# Python.net
KiCad netlist of a schematic drawn in Altium Designer
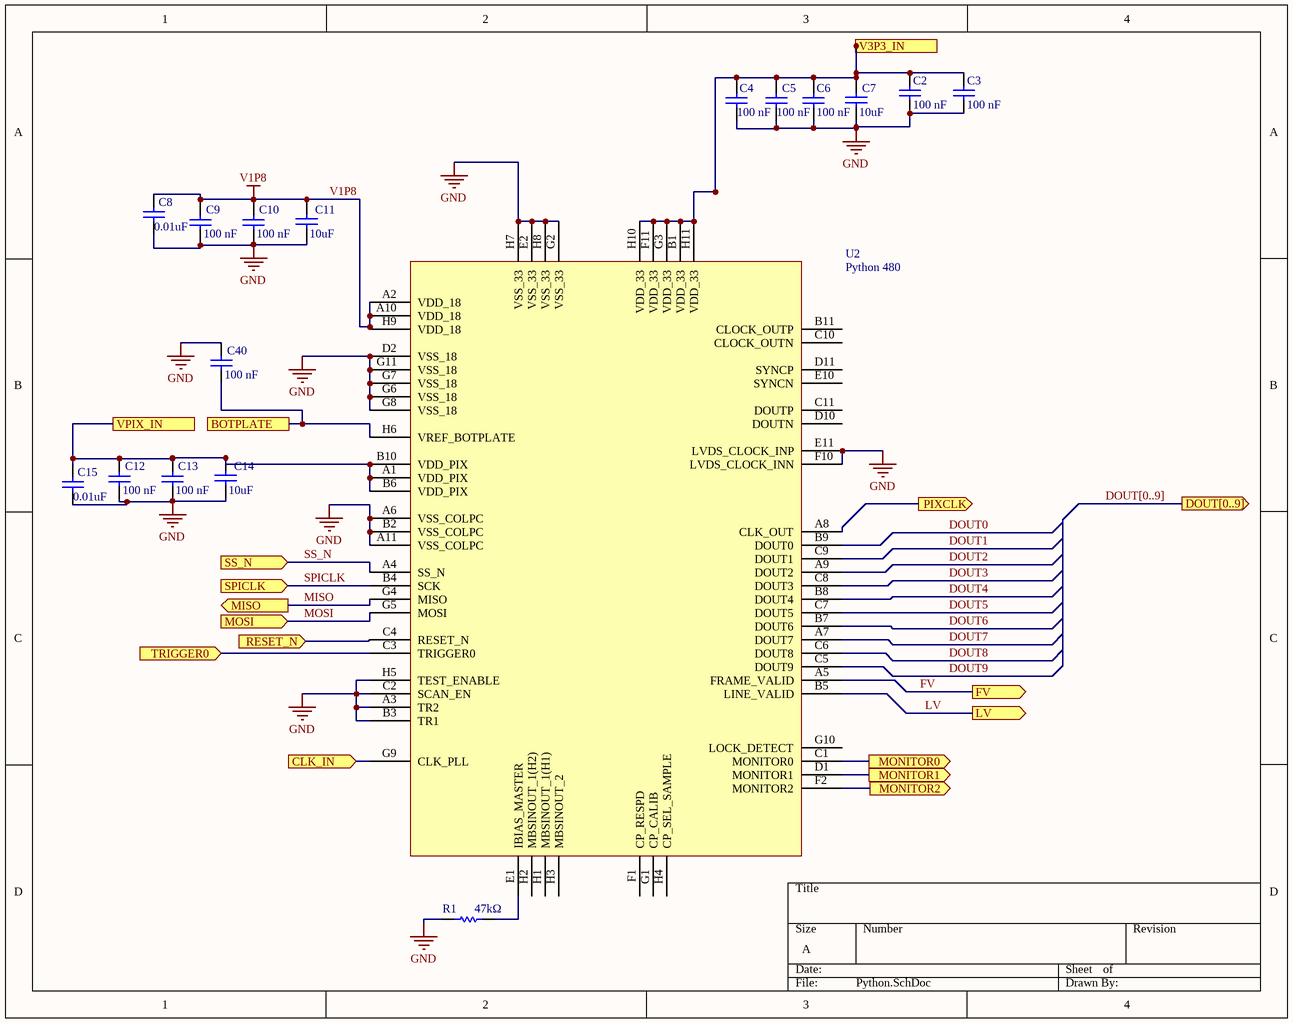
[diagram p0: Python.SchDoc]

(export (version "E")
  (design (tool "Eeschema 10.0.6"))
  (components
    (comp (ref "C2")
      (value "GRM033C71C104KE14D")
      (footprint "PCB-v6eq6etc9p7u7qdkgnno-1")
      (description "0.1 µF ±10% 16V Ceramic Capacitor X7S 0201 (0603 Metric)")
      (fields (field (name "CAPACITANCE") "100 nF"))
      (libsource (lib "Python_Imaging_1") (part "CMP-cc290632c88a13ee-3"))
    )
    (comp (ref "C3")
      (value "GRM033C71C104KE14D")
      (footprint "PCB-v6eq6etc9p7u7qdkgnno-1")
      (description "0.1 µF ±10% 16V Ceramic Capacitor X7S 0201 (0603 Metric)")
      (fields (field (name "CAPACITANCE") "100 nF"))
      (libsource (lib "Python_Imaging_1") (part "CMP-cc290632c88a13ee-3"))
    )
    (comp (ref "C4")
      (value "GRM033C71C104KE14D")
      (footprint "PCB-v6eq6etc9p7u7qdkgnno-1")
      (description "0.1 µF ±10% 16V Ceramic Capacitor X7S 0201 (0603 Metric)")
      (fields (field (name "CAPACITANCE") "100 nF"))
      (libsource (lib "Python_Imaging_1") (part "CMP-cc290632c88a13ee-3"))
    )
    (comp (ref "C5")
      (value "GRM033C71C104KE14D")
      (footprint "PCB-v6eq6etc9p7u7qdkgnno-1")
      (description "0.1 µF ±10% 16V Ceramic Capacitor X7S 0201 (0603 Metric)")
      (fields (field (name "CAPACITANCE") "100 nF"))
      (libsource (lib "Python_Imaging_1") (part "CMP-cc290632c88a13ee-3"))
    )
    (comp (ref "C6")
      (value "GRM033C71C104KE14D")
      (footprint "PCB-v6eq6etc9p7u7qdkgnno-1")
      (description "0.1 µF ±10% 16V Ceramic Capacitor X7S 0201 (0603 Metric)")
      (fields (field (name "CAPACITANCE") "100 nF"))
      (libsource (lib "Python_Imaging_1") (part "CMP-cc290632c88a13ee-3"))
    )
    (comp (ref "C7")
      (value "GRM155R61A106ME11D")
      (footprint "PCB-uspfzztrpe7hn2xlyjz9-1")
      (description "10 µF ±20% 10V Ceramic Capacitor X5R 0402 (1005 Metric)")
      (fields (field (name "CAPACITANCE") "10uF"))
      (libsource (lib "Python_Imaging_1") (part "CMP-eacb22ede71a350c-8"))
    )
    (comp (ref "C8")
      (value "GRM033R71A103KA01D")
      (footprint "PCB-v6eq6etc9p7u7qdkgnno-1")
      (description "10000 pF ±10% 10V Ceramic Capacitor X7R 0201 (0603 Metric)")
      (fields (field (name "CAPACITANCE") "0.01uF"))
      (libsource (lib "Python_Imaging_1") (part "CMP-19299660-4"))
    )
    (comp (ref "C9")
      (value "GRM033C71C104KE14D")
      (footprint "PCB-v6eq6etc9p7u7qdkgnno-1")
      (description "0.1 µF ±10% 16V Ceramic Capacitor X7S 0201 (0603 Metric)")
      (fields (field (name "CAPACITANCE") "100 nF"))
      (libsource (lib "Python_Imaging_1") (part "CMP-cc290632c88a13ee-3"))
    )
    (comp (ref "C10")
      (value "GRM033C71C104KE14D")
      (footprint "PCB-v6eq6etc9p7u7qdkgnno-1")
      (description "0.1 µF ±10% 16V Ceramic Capacitor X7S 0201 (0603 Metric)")
      (fields (field (name "CAPACITANCE") "100 nF"))
      (libsource (lib "Python_Imaging_1") (part "CMP-cc290632c88a13ee-3"))
    )
    (comp (ref "C11")
      (value "GRM155R61A106ME11D")
      (footprint "PCB-uspfzztrpe7hn2xlyjz9-1")
      (description "10 µF ±20% 10V Ceramic Capacitor X5R 0402 (1005 Metric)")
      (fields (field (name "CAPACITANCE") "10uF"))
      (libsource (lib "Python_Imaging_1") (part "CMP-eacb22ede71a350c-8"))
    )
    (comp (ref "C12")
      (value "GRM033C71C104KE14D")
      (footprint "PCB-v6eq6etc9p7u7qdkgnno-1")
      (description "0.1 µF ±10% 16V Ceramic Capacitor X7S 0201 (0603 Metric)")
      (fields (field (name "CAPACITANCE") "100 nF"))
      (libsource (lib "Python_Imaging_1") (part "CMP-cc290632c88a13ee-3"))
    )
    (comp (ref "C13")
      (value "GRM033C71C104KE14D")
      (footprint "PCB-v6eq6etc9p7u7qdkgnno-1")
      (description "0.1 µF ±10% 16V Ceramic Capacitor X7S 0201 (0603 Metric)")
      (fields (field (name "CAPACITANCE") "100 nF"))
      (libsource (lib "Python_Imaging_1") (part "CMP-cc290632c88a13ee-3"))
    )
    (comp (ref "C14")
      (value "GRM155R61A106ME11D")
      (footprint "PCB-uspfzztrpe7hn2xlyjz9-1")
      (description "10 µF ±20% 10V Ceramic Capacitor X5R 0402 (1005 Metric)")
      (fields (field (name "CAPACITANCE") "10uF"))
      (libsource (lib "Python_Imaging_1") (part "CMP-eacb22ede71a350c-8"))
    )
    (comp (ref "C15")
      (value "GRM033R71A103KA01D")
      (footprint "PCB-v6eq6etc9p7u7qdkgnno-1")
      (description "10000 pF ±10% 10V Ceramic Capacitor X7R 0201 (0603 Metric)")
      (fields (field (name "CAPACITANCE") "0.01uF"))
      (libsource (lib "Python_Imaging_1") (part "CMP-19299660-4"))
    )
    (comp (ref "C40")
      (value "GRM033C71C104KE14D")
      (footprint "PCB-v6eq6etc9p7u7qdkgnno-1")
      (description "0.1 µF ±10% 16V Ceramic Capacitor X7S 0201 (0603 Metric)")
      (fields (field (name "CAPACITANCE") "100 nF"))
      (libsource (lib "Python_Imaging_1") (part "CMP-cc290632c88a13ee-3"))
    )
    (comp (ref "R1")
      (value "ERJ-1GNF4702C")
      (footprint "PCB-7g93mzch2qc2q3jid3ok-1")
      (description "47 kOhms ±1% 0.05W, 1/20W Chip Resistor 0201 (0603 Metric) Automotive AEC-Q200 Thick Film")
      (fields (field (name "RESISTANCE") "47kΩ"))
      (libsource (lib "Python_Imaging_1") (part "CMP-1848656-4"))
    )
    (comp (ref "U2")
      (value "Python 480")
      (footprint "Python 480")
      (description "image sensor from ONSemi")
      (libsource (lib "Python_Imaging_1") (part "SYM-zuljd18wlr9in3443qu3-1"))
    )
  )
  (nets
    (net (code "1") (name "/BOTPLATE") (class "Default")
      (node (ref "C40") (pin "1") (pinfunction "1_1") (pintype "passive"))
      (node (ref "U2") (pin "H6") (pinfunction "VREF_BOTPLATE_H6") (pintype "passive"))
    )
    (net (code "2") (name "/CLK_IN") (class "Default")
      (node (ref "U2") (pin "G9") (pinfunction "CLK_PLL_G9") (pintype "passive"))
    )
    (net (code "3") (name "/DOUT0") (class "Default")
      (node (ref "U2") (pin "B9") (pinfunction "DOUT0_B9") (pintype "passive"))
    )
    (net (code "4") (name "/DOUT1") (class "Default")
      (node (ref "U2") (pin "C9") (pinfunction "DOUT1_C9") (pintype "passive"))
    )
    (net (code "5") (name "/DOUT2") (class "Default")
      (node (ref "U2") (pin "A9") (pinfunction "DOUT2_A9") (pintype "passive"))
    )
    (net (code "6") (name "/DOUT3") (class "Default")
      (node (ref "U2") (pin "C8") (pinfunction "DOUT3_C8") (pintype "passive"))
    )
    (net (code "7") (name "/DOUT4") (class "Default")
      (node (ref "U2") (pin "B8") (pinfunction "DOUT4_B8") (pintype "passive"))
    )
    (net (code "8") (name "/DOUT5") (class "Default")
      (node (ref "U2") (pin "C7") (pinfunction "DOUT5_C7") (pintype "passive"))
    )
    (net (code "9") (name "/DOUT6") (class "Default")
      (node (ref "U2") (pin "B7") (pinfunction "DOUT6_B7") (pintype "passive"))
    )
    (net (code "10") (name "/DOUT7") (class "Default")
      (node (ref "U2") (pin "A7") (pinfunction "DOUT7_A7") (pintype "passive"))
    )
    (net (code "11") (name "/DOUT8") (class "Default")
      (node (ref "U2") (pin "C6") (pinfunction "DOUT8_C6") (pintype "passive"))
    )
    (net (code "12") (name "/DOUT9") (class "Default")
      (node (ref "U2") (pin "C5") (pinfunction "DOUT9_C5") (pintype "passive"))
    )
    (net (code "14") (name "/FV") (class "Default")
      (node (ref "U2") (pin "A5") (pinfunction "FRAME_VALID_A5") (pintype "passive"))
    )
    (net (code "15") (name "/LV") (class "Default")
      (node (ref "U2") (pin "B5") (pinfunction "LINE_VALID_B5") (pintype "passive"))
    )
    (net (code "16") (name "/MISO") (class "Default")
      (node (ref "U2") (pin "G4") (pinfunction "MISO_G4") (pintype "passive"))
    )
    (net (code "17") (name "/MONITOR0") (class "Default")
      (node (ref "U2") (pin "C1") (pinfunction "MONITOR0_C1") (pintype "passive"))
    )
    (net (code "18") (name "/MONITOR1") (class "Default")
      (node (ref "U2") (pin "D1") (pinfunction "MONITOR1_D1") (pintype "passive"))
    )
    (net (code "19") (name "/MONITOR2") (class "Default")
      (node (ref "U2") (pin "F2") (pinfunction "MONITOR2_F2") (pintype "passive"))
    )
    (net (code "20") (name "/MOSI") (class "Default")
      (node (ref "U2") (pin "G5") (pinfunction "MOSI_G5") (pintype "passive"))
    )
    (net (code "21") (name "/PIXCLK") (class "Default")
      (node (ref "U2") (pin "A8") (pinfunction "CLK_OUT_A8") (pintype "passive"))
    )
    (net (code "22") (name "/RESET_N") (class "Default")
      (node (ref "U2") (pin "C4") (pinfunction "RESET_N_C4") (pintype "passive"))
    )
    (net (code "23") (name "/SPICLK") (class "Default")
      (node (ref "U2") (pin "B4") (pinfunction "SCK_B4") (pintype "passive"))
    )
    (net (code "24") (name "/SS_N") (class "Default")
      (node (ref "U2") (pin "A4") (pinfunction "SS_N_A4") (pintype "passive"))
    )
    (net (code "25") (name "/TRIGGER0") (class "Default")
      (node (ref "U2") (pin "C3") (pinfunction "TRIGGER0_C3") (pintype "passive"))
    )
    (net (code "26") (name "/V3P3_IN") (class "Default")
      (node (ref "C2") (pin "2") (pinfunction "2_2") (pintype "passive"))
      (node (ref "C3") (pin "2") (pinfunction "2_2") (pintype "passive"))
      (node (ref "C4") (pin "2") (pinfunction "2_2") (pintype "passive"))
      (node (ref "C5") (pin "2") (pinfunction "2_2") (pintype "passive"))
      (node (ref "C6") (pin "2") (pinfunction "2_2") (pintype "passive"))
      (node (ref "C7") (pin "1") (pinfunction "1_1") (pintype "passive"))
      (node (ref "U2") (pin "B1") (pinfunction "VDD_33_B1") (pintype "passive"))
      (node (ref "U2") (pin "F11") (pinfunction "VDD_33_F11") (pintype "passive"))
      (node (ref "U2") (pin "G3") (pinfunction "VDD_33_G3") (pintype "passive"))
      (node (ref "U2") (pin "H10") (pinfunction "VDD_33_H10") (pintype "passive"))
      (node (ref "U2") (pin "H11") (pinfunction "VDD_33_H11") (pintype "passive"))
    )
    (net (code "27") (name "/VPIX_IN") (class "Default")
      (node (ref "C12") (pin "2") (pinfunction "2_2") (pintype "passive"))
      (node (ref "C13") (pin "2") (pinfunction "2_2") (pintype "passive"))
      (node (ref "C14") (pin "1") (pinfunction "1_1") (pintype "passive"))
      (node (ref "C15") (pin "2") (pinfunction "2_2") (pintype "passive"))
      (node (ref "U2") (pin "A1") (pinfunction "VDD_PIX_A1") (pintype "passive"))
      (node (ref "U2") (pin "B10") (pinfunction "VDD_PIX_B10") (pintype "passive"))
      (node (ref "U2") (pin "B6") (pinfunction "VDD_PIX_B6") (pintype "passive"))
    )
    (net (code "28") (name "GND") (class "Default")
      (node (ref "C10") (pin "1") (pinfunction "1_1") (pintype "passive"))
      (node (ref "C11") (pin "2") (pinfunction "2_2") (pintype "passive"))
      (node (ref "C12") (pin "1") (pinfunction "1_1") (pintype "passive"))
      (node (ref "C13") (pin "1") (pinfunction "1_1") (pintype "passive"))
      (node (ref "C14") (pin "2") (pinfunction "2_2") (pintype "passive"))
      (node (ref "C15") (pin "1") (pinfunction "1_1") (pintype "passive"))
      (node (ref "C2") (pin "1") (pinfunction "1_1") (pintype "passive"))
      (node (ref "C3") (pin "1") (pinfunction "1_1") (pintype "passive"))
      (node (ref "C4") (pin "1") (pinfunction "1_1") (pintype "passive"))
      (node (ref "C40") (pin "2") (pinfunction "2_2") (pintype "passive"))
      (node (ref "C5") (pin "1") (pinfunction "1_1") (pintype "passive"))
      (node (ref "C6") (pin "1") (pinfunction "1_1") (pintype "passive"))
      (node (ref "C7") (pin "2") (pinfunction "2_2") (pintype "passive"))
      (node (ref "C8") (pin "1") (pinfunction "1_1") (pintype "passive"))
      (node (ref "C9") (pin "1") (pinfunction "1_1") (pintype "passive"))
      (node (ref "R1") (pin "1") (pinfunction "1_1") (pintype "passive"))
      (node (ref "U2") (pin "A11") (pinfunction "VSS_COLPC_A11") (pintype "passive"))
      (node (ref "U2") (pin "A3") (pinfunction "TR2_A3") (pintype "passive"))
      (node (ref "U2") (pin "A6") (pinfunction "VSS_COLPC_A6") (pintype "passive"))
      (node (ref "U2") (pin "B2") (pinfunction "VSS_COLPC_B2") (pintype "passive"))
      (node (ref "U2") (pin "B3") (pinfunction "TR1_B3") (pintype "passive"))
      (node (ref "U2") (pin "C2") (pinfunction "SCAN_EN_C2") (pintype "passive"))
      (node (ref "U2") (pin "D2") (pinfunction "VSS_18_D2") (pintype "passive"))
      (node (ref "U2") (pin "E11") (pinfunction "LVDS_CLOCK_INP_E11") (pintype "passive"))
      (node (ref "U2") (pin "E2") (pinfunction "VSS_33_E2") (pintype "passive"))
      (node (ref "U2") (pin "F10") (pinfunction "LVDS_CLOCK_INN_F10") (pintype "passive"))
      (node (ref "U2") (pin "G11") (pinfunction "VSS_18_G11") (pintype "passive"))
      (node (ref "U2") (pin "G2") (pinfunction "VSS_33_G2") (pintype "passive"))
      (node (ref "U2") (pin "G6") (pinfunction "VSS_18_G6") (pintype "passive"))
      (node (ref "U2") (pin "G7") (pinfunction "VSS_18_G7") (pintype "passive"))
      (node (ref "U2") (pin "G8") (pinfunction "VSS_18_G8") (pintype "passive"))
      (node (ref "U2") (pin "H5") (pinfunction "TEST_ENABLE_H5") (pintype "passive"))
      (node (ref "U2") (pin "H7") (pinfunction "VSS_33_H7") (pintype "passive"))
      (node (ref "U2") (pin "H8") (pinfunction "VSS_33_H8") (pintype "passive"))
    )
    (net (code "29") (name "Net-(U2-IBIAS_MASTER)") (class "Default")
      (node (ref "R1") (pin "2") (pinfunction "2_2") (pintype "passive"))
      (node (ref "U2") (pin "E1") (pinfunction "IBIAS_MASTER_E1") (pintype "passive"))
    )
    (net (code "30") (name "V1P8") (class "Default")
      (node (ref "C10") (pin "2") (pinfunction "2_2") (pintype "passive"))
      (node (ref "C11") (pin "1") (pinfunction "1_1") (pintype "passive"))
      (node (ref "C8") (pin "2") (pinfunction "2_2") (pintype "passive"))
      (node (ref "C9") (pin "2") (pinfunction "2_2") (pintype "passive"))
      (node (ref "U2") (pin "A10") (pinfunction "VDD_18_A10") (pintype "passive"))
      (node (ref "U2") (pin "A2") (pinfunction "VDD_18_A2") (pintype "passive"))
      (node (ref "U2") (pin "H9") (pinfunction "VDD_18_H9") (pintype "passive"))
    )
    (net (code "31") (name "unconnected-(U2-CLOCK_OUTN-PadC10)") (class "Default")
      (node (ref "U2") (pin "C10") (pinfunction "CLOCK_OUTN_C10") (pintype "passive"))
    )
    (net (code "32") (name "unconnected-(U2-CLOCK_OUTP-PadB11)") (class "Default")
      (node (ref "U2") (pin "B11") (pinfunction "CLOCK_OUTP_B11") (pintype "passive"))
    )
    (net (code "33") (name "unconnected-(U2-CP_CALIB-PadG1)") (class "Default")
      (node (ref "U2") (pin "G1") (pinfunction "CP_CALIB_G1") (pintype "passive"))
    )
    (net (code "34") (name "unconnected-(U2-CP_RESPD-PadF1)") (class "Default")
      (node (ref "U2") (pin "F1") (pinfunction "CP_RESPD_F1") (pintype "passive"))
    )
    (net (code "35") (name "unconnected-(U2-CP_SEL_SAMPLE-PadH4)") (class "Default")
      (node (ref "U2") (pin "H4") (pinfunction "CP_SEL_SAMPLE_H4") (pintype "passive"))
    )
    (net (code "36") (name "unconnected-(U2-DOUTN-PadD10)") (class "Default")
      (node (ref "U2") (pin "D10") (pinfunction "DOUTN_D10") (pintype "passive"))
    )
    (net (code "37") (name "unconnected-(U2-DOUTP-PadC11)") (class "Default")
      (node (ref "U2") (pin "C11") (pinfunction "DOUTP_C11") (pintype "passive"))
    )
    (net (code "38") (name "unconnected-(U2-LOCK_DETECT-PadG10)") (class "Default")
      (node (ref "U2") (pin "G10") (pinfunction "LOCK_DETECT_G10") (pintype "passive"))
    )
    (net (code "39") (name "unconnected-(U2-MBSINOUT_1(H1)-PadH1)") (class "Default")
      (node (ref "U2") (pin "H1") (pinfunction "MBSINOUT_1(H1)_H1") (pintype "passive"))
    )
    (net (code "40") (name "unconnected-(U2-MBSINOUT_1(H2)-PadH2)") (class "Default")
      (node (ref "U2") (pin "H2") (pinfunction "MBSINOUT_1(H2)_H2") (pintype "passive"))
    )
    (net (code "41") (name "unconnected-(U2-MBSINOUT_2-PadH3)") (class "Default")
      (node (ref "U2") (pin "H3") (pinfunction "MBSINOUT_2_H3") (pintype "passive"))
    )
    (net (code "42") (name "unconnected-(U2-SYNCN-PadE10)") (class "Default")
      (node (ref "U2") (pin "E10") (pinfunction "SYNCN_E10") (pintype "passive"))
    )
    (net (code "43") (name "unconnected-(U2-SYNCP-PadD11)") (class "Default")
      (node (ref "U2") (pin "D11") (pinfunction "SYNCP_D11") (pintype "passive"))
    )
  )
)
